# LAB_20200315_1_UseFlexSensorToTestServo.net
KiCad netlist of a schematic drawn in EAGLE
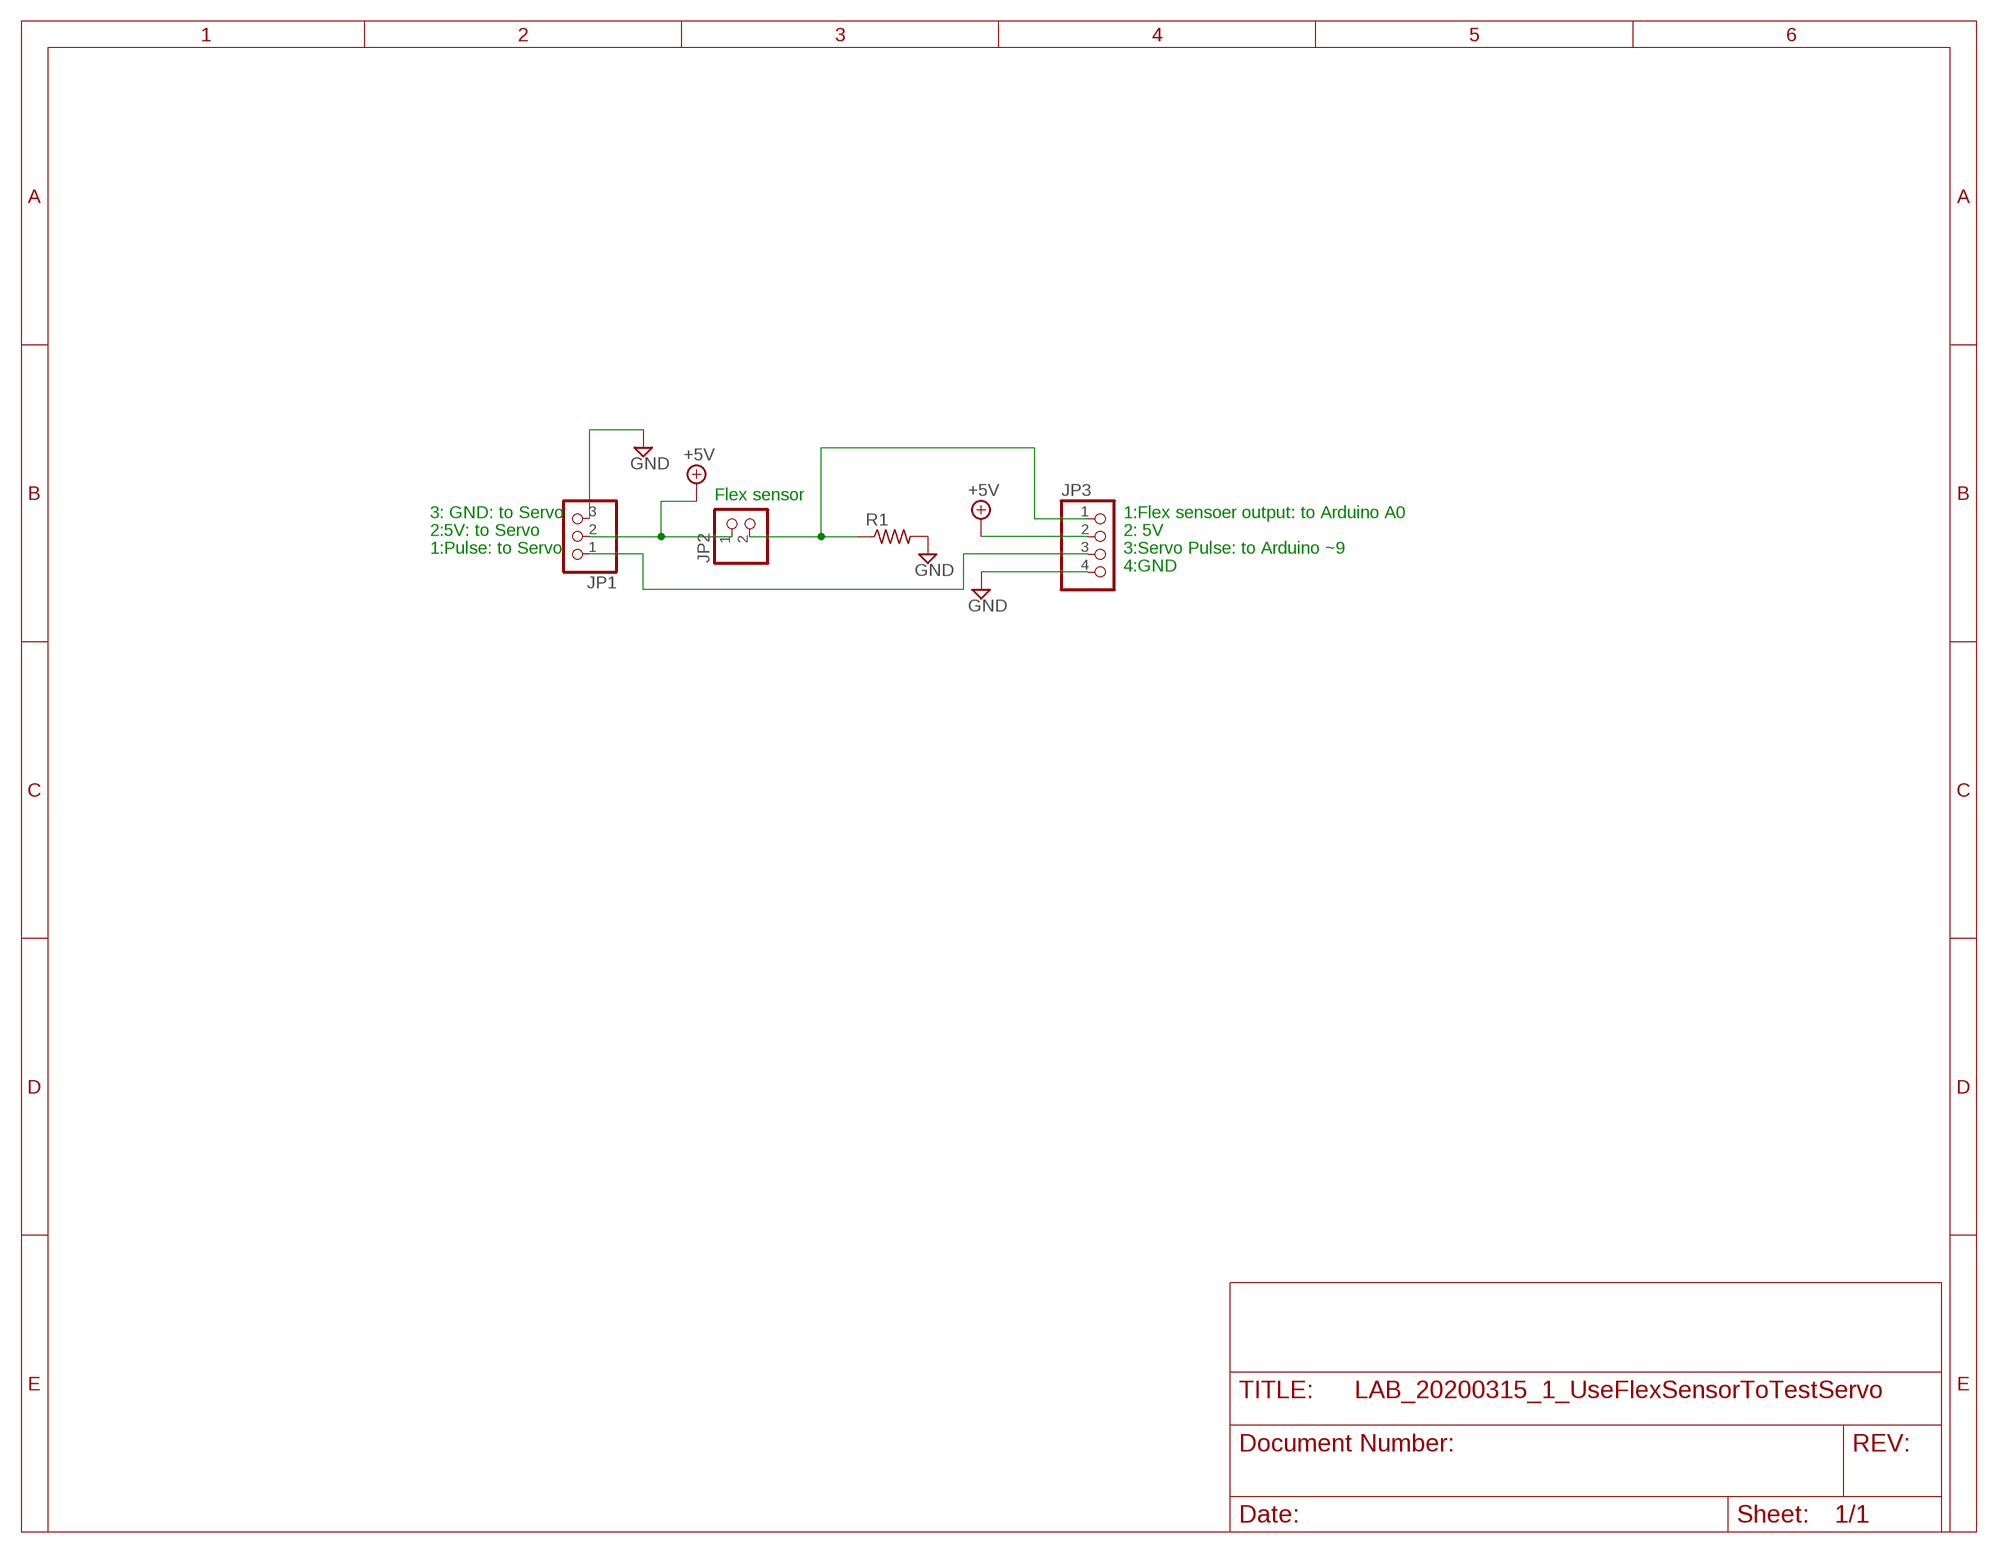
[diagram p0: schematic, sheet 1]

(export (version "E")
  (design (tool "Eeschema 10.0.6"))
  (components
    (comp (ref "JP1")
      (value "PINHD-1X3")
      (footprint "eagle-import:1X03")
      (libsource (lib "eagle-import") (part "PINHD-1X3"))
    )
    (comp (ref "JP2")
      (value "PINHD-1X2")
      (footprint "eagle-import:1X02")
      (libsource (lib "eagle-import") (part "PINHD-1X2"))
    )
    (comp (ref "JP3")
      (value "PINHD-1X4")
      (footprint "eagle-import:1X04")
      (libsource (lib "eagle-import") (part "PINHD-1X4"))
    )
    (comp (ref "R1")
      (value "R-US_0207/12")
      (footprint "eagle-import:0207_12")
      (libsource (lib "eagle-import") (part "R-US_0207/12"))
    )
  )
  (nets
    (net (code "1") (name "+5V") (class "Default")
      (node (ref "JP1") (pin "2") (pinfunction "2_2") (pintype "passive"))
      (node (ref "JP2") (pin "1") (pinfunction "1_1") (pintype "passive"))
      (node (ref "JP3") (pin "2") (pinfunction "2_2") (pintype "passive"))
    )
    (net (code "2") (name "GND") (class "Default")
      (node (ref "JP1") (pin "3") (pinfunction "3_3") (pintype "passive"))
      (node (ref "JP3") (pin "4") (pinfunction "4_4") (pintype "passive"))
      (node (ref "R1") (pin "2") (pinfunction "2_2") (pintype "passive"))
    )
    (net (code "3") (name "Net-(JP1-Pad1)") (class "Default")
      (node (ref "JP1") (pin "1") (pinfunction "1_1") (pintype "passive"))
      (node (ref "JP3") (pin "3") (pinfunction "3_3") (pintype "passive"))
    )
    (net (code "4") (name "Net-(JP2-Pad2)") (class "Default")
      (node (ref "JP2") (pin "2") (pinfunction "2_2") (pintype "passive"))
      (node (ref "JP3") (pin "1") (pinfunction "1_1") (pintype "passive"))
      (node (ref "R1") (pin "1") (pinfunction "1_1") (pintype "passive"))
    )
  )
)
